# mppt.net
KiCad netlist of a schematic drawn in EAGLE
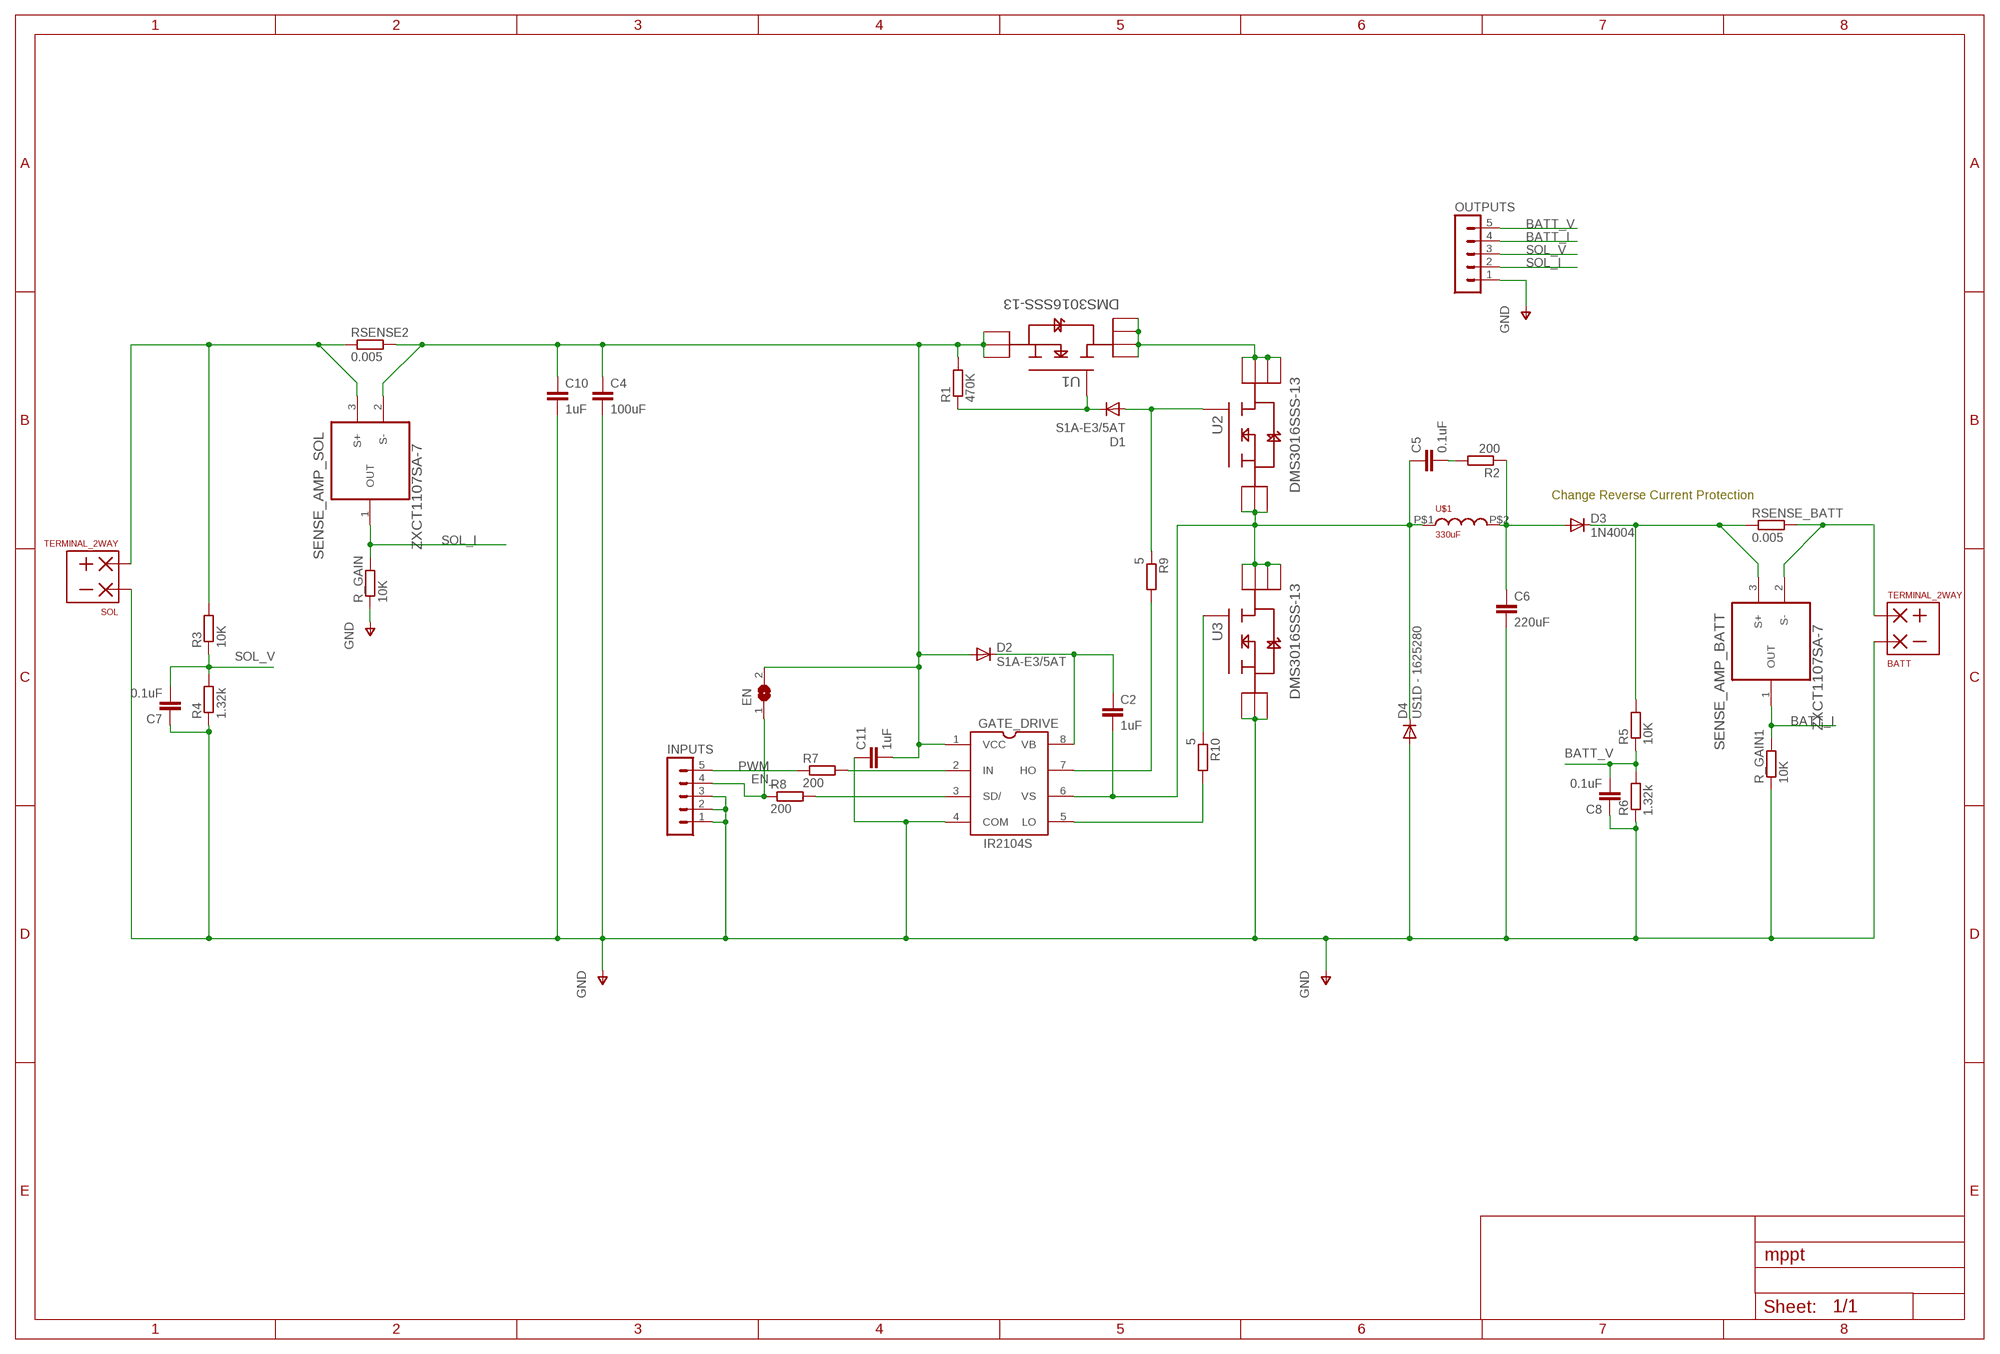
[diagram p0: schematic, sheet 1]

(export (version "E")
  (design (tool "Eeschema 10.0.6"))
  (components
    (comp (ref "BATT")
      (value "TERMINAL_2WAY")
      (footprint "eagle-import:TERMINAL_2WAY")
      (libsource (lib "eagle-import") (part "TERMINAL_2WAY"))
    )
    (comp (ref "C2")
      (value "1uF")
      (footprint "eagle-import:C0805K")
      (libsource (lib "eagle-import") (part "C-EUC0805K"))
    )
    (comp (ref "C4")
      (value "100uF")
      (footprint "eagle-import:C025-050X050")
      (libsource (lib "eagle-import") (part "C-EU025-050X050"))
    )
    (comp (ref "C5")
      (value "0.1uF")
      (footprint "eagle-import:C0805K")
      (libsource (lib "eagle-import") (part "C-EUC0805K"))
    )
    (comp (ref "C6")
      (value "220uF")
      (footprint "eagle-import:C025-050X050")
      (libsource (lib "eagle-import") (part "C-EU025-050X050"))
    )
    (comp (ref "C7")
      (value "0.1uF")
      (footprint "eagle-import:C0805K")
      (libsource (lib "eagle-import") (part "C-EUC0805K"))
    )
    (comp (ref "C8")
      (value "0.1uF")
      (footprint "eagle-import:C0805K")
      (libsource (lib "eagle-import") (part "C-EUC0805K"))
    )
    (comp (ref "C10")
      (value "1uF")
      (footprint "eagle-import:C0805K")
      (libsource (lib "eagle-import") (part "C-EUC0805K"))
    )
    (comp (ref "C11")
      (value "1uF")
      (footprint "eagle-import:C0805K")
      (libsource (lib "eagle-import") (part "C-EUC0805K"))
    )
    (comp (ref "D1")
      (value "S1A-E3/5AT")
      (footprint "eagle-import:DO-214AC")
      (libsource (lib "eagle-import") (part "DIODE-DO-214AC"))
    )
    (comp (ref "D2")
      (value "S1A-E3/5AT")
      (footprint "eagle-import:DO-214AC")
      (libsource (lib "eagle-import") (part "DIODE-DO-214AC"))
    )
    (comp (ref "D3")
      (value "1N4004")
      (footprint "eagle-import:DO41-10")
      (libsource (lib "eagle-import") (part "1N4004"))
    )
    (comp (ref "D4")
      (value "US1D - 1625280")
      (footprint "eagle-import:DO-214AC")
      (libsource (lib "eagle-import") (part "DIODE-DO-214AC"))
    )
    (comp (ref "EN") (value "SJ") (footprint "eagle-import:SJ") (libsource (lib "eagle-import") (part "SJ")))
    (comp (ref "GATE_DRIVE")
      (value "IR2104S")
      (footprint "eagle-import:IR2104S")
      (libsource (lib "eagle-import") (part "IR2104S"))
    )
    (comp (ref "INPUTS")
      (value "MA05-1")
      (footprint "eagle-import:MA05-1")
      (libsource (lib "eagle-import") (part "MA05-1"))
    )
    (comp (ref "OUTPUTS")
      (value "MA05-1")
      (footprint "eagle-import:MA05-1")
      (libsource (lib "eagle-import") (part "MA05-1"))
    )
    (comp (ref "R1")
      (value "470K")
      (footprint "eagle-import:M0805")
      (libsource (lib "eagle-import") (part "R-EU_M0805"))
    )
    (comp (ref "R2")
      (value "200")
      (footprint "eagle-import:M0805")
      (libsource (lib "eagle-import") (part "R-EU_M0805"))
    )
    (comp (ref "R3")
      (value "10K")
      (footprint "eagle-import:M0805")
      (libsource (lib "eagle-import") (part "R-EU_M0805"))
    )
    (comp (ref "R4")
      (value "1.32k")
      (footprint "eagle-import:M0805")
      (libsource (lib "eagle-import") (part "R-EU_M0805"))
    )
    (comp (ref "R5")
      (value "10K")
      (footprint "eagle-import:M0805")
      (libsource (lib "eagle-import") (part "R-EU_M0805"))
    )
    (comp (ref "R6")
      (value "1.32k")
      (footprint "eagle-import:M0805")
      (libsource (lib "eagle-import") (part "R-EU_M0805"))
    )
    (comp (ref "R7")
      (value "200")
      (footprint "eagle-import:M0805")
      (libsource (lib "eagle-import") (part "R-EU_M0805"))
    )
    (comp (ref "R8")
      (value "200")
      (footprint "eagle-import:M0805")
      (libsource (lib "eagle-import") (part "R-EU_M0805"))
    )
    (comp (ref "R9")
      (value "5")
      (footprint "eagle-import:M0805")
      (libsource (lib "eagle-import") (part "R-EU_M0805"))
    )
    (comp (ref "R10")
      (value "5")
      (footprint "eagle-import:M0805")
      (libsource (lib "eagle-import") (part "R-EU_M0805"))
    )
    (comp (ref "RSENSE2")
      (value "0.005")
      (footprint "eagle-import:R2512")
      (libsource (lib "eagle-import") (part "R-EU_R2512"))
    )
    (comp (ref "RSENSE_BATT")
      (value "0.005")
      (footprint "eagle-import:R2512")
      (libsource (lib "eagle-import") (part "R-EU_R2512"))
    )
    (comp (ref "R_GAIN")
      (value "10K")
      (footprint "eagle-import:M0805")
      (libsource (lib "eagle-import") (part "R-EU_M0805"))
    )
    (comp (ref "R_GAIN1")
      (value "10K")
      (footprint "eagle-import:M0805")
      (libsource (lib "eagle-import") (part "R-EU_M0805"))
    )
    (comp (ref "SENSE_AMP_BATT")
      (value "ZXCT1107SA-7")
      (footprint "eagle-import:SOT91P240X110-3N")
      (libsource (lib "eagle-import") (part "ZXCT1107SA-7"))
    )
    (comp (ref "SENSE_AMP_SOL")
      (value "ZXCT1107SA-7")
      (footprint "eagle-import:SOT91P240X110-3N")
      (libsource (lib "eagle-import") (part "ZXCT1107SA-7"))
    )
    (comp (ref "SOL")
      (value "TERMINAL_2WAY")
      (footprint "eagle-import:TERMINAL_2WAY")
      (libsource (lib "eagle-import") (part "TERMINAL_2WAY"))
    )
    (comp (ref "U$1")
      (value "330uF")
      (footprint "eagle-import:BOURNS_SDR1806")
      (libsource (lib "eagle-import") (part "INDUC_BOURNES_SDR1806"))
    )
    (comp (ref "U1")
      (value "DMS3016SSS-13")
      (footprint "eagle-import:SOIC127P600X175-8N")
      (libsource (lib "eagle-import") (part "DMS3016SSS-13"))
    )
    (comp (ref "U2")
      (value "DMS3016SSS-13")
      (footprint "eagle-import:SOIC127P600X175-8N")
      (libsource (lib "eagle-import") (part "DMS3016SSS-13"))
    )
    (comp (ref "U3")
      (value "DMS3016SSS-13")
      (footprint "eagle-import:SOIC127P600X175-8N")
      (libsource (lib "eagle-import") (part "DMS3016SSS-13"))
    )
  )
  (nets
    (net (code "1") (name "/BATT_I") (class "Default")
      (node (ref "OUTPUTS") (pin "4") (pinfunction "4_4") (pintype "passive"))
      (node (ref "R_GAIN1") (pin "2") (pinfunction "2_2") (pintype "passive"))
      (node (ref "SENSE_AMP_BATT") (pin "1") (pinfunction "OUT_1") (pintype "output"))
    )
    (net (code "2") (name "/BATT_V") (class "Default")
      (node (ref "C8") (pin "2") (pinfunction "2_2") (pintype "passive"))
      (node (ref "OUTPUTS") (pin "5") (pinfunction "5_5") (pintype "passive"))
      (node (ref "R5") (pin "1") (pinfunction "1_1") (pintype "passive"))
      (node (ref "R6") (pin "2") (pinfunction "2_2") (pintype "passive"))
    )
    (net (code "3") (name "/EN_") (class "Default")
      (node (ref "EN") (pin "1") (pinfunction "1_1") (pintype "passive"))
      (node (ref "INPUTS") (pin "4") (pinfunction "4_4") (pintype "passive"))
      (node (ref "R8") (pin "1") (pinfunction "1_1") (pintype "passive"))
    )
    (net (code "4") (name "/PWM") (class "Default")
      (node (ref "INPUTS") (pin "5") (pinfunction "5_5") (pintype "passive"))
      (node (ref "R7") (pin "1") (pinfunction "1_1") (pintype "passive"))
    )
    (net (code "5") (name "/SOL_I") (class "Default")
      (node (ref "OUTPUTS") (pin "2") (pinfunction "2_2") (pintype "passive"))
      (node (ref "R_GAIN") (pin "2") (pinfunction "2_2") (pintype "passive"))
      (node (ref "SENSE_AMP_SOL") (pin "1") (pinfunction "OUT_1") (pintype "output"))
    )
    (net (code "6") (name "/SOL_V") (class "Default")
      (node (ref "C7") (pin "2") (pinfunction "2_2") (pintype "passive"))
      (node (ref "OUTPUTS") (pin "3") (pinfunction "3_3") (pintype "passive"))
      (node (ref "R3") (pin "1") (pinfunction "1_1") (pintype "passive"))
      (node (ref "R4") (pin "2") (pinfunction "2_2") (pintype "passive"))
    )
    (net (code "7") (name "GND") (class "Default")
      (node (ref "BATT") (pin "P$2") (pinfunction "P$2_P$2") (pintype "bidirectional"))
      (node (ref "C10") (pin "2") (pinfunction "2_2") (pintype "passive"))
      (node (ref "C11") (pin "1") (pinfunction "1_1") (pintype "passive"))
      (node (ref "C4") (pin "2") (pinfunction "2_2") (pintype "passive"))
      (node (ref "C6") (pin "2") (pinfunction "2_2") (pintype "passive"))
      (node (ref "C7") (pin "1") (pinfunction "1_1") (pintype "passive"))
      (node (ref "C8") (pin "1") (pinfunction "1_1") (pintype "passive"))
      (node (ref "D4") (pin "A") (pinfunction "A_A") (pintype "passive"))
      (node (ref "GATE_DRIVE") (pin "4") (pinfunction "COM_4") (pintype "bidirectional"))
      (node (ref "INPUTS") (pin "1") (pinfunction "1_1") (pintype "passive"))
      (node (ref "INPUTS") (pin "2") (pinfunction "2_2") (pintype "passive"))
      (node (ref "INPUTS") (pin "3") (pinfunction "3_3") (pintype "passive"))
      (node (ref "OUTPUTS") (pin "1") (pinfunction "1_1") (pintype "passive"))
      (node (ref "R4") (pin "1") (pinfunction "1_1") (pintype "passive"))
      (node (ref "R6") (pin "1") (pinfunction "1_1") (pintype "passive"))
      (node (ref "R_GAIN") (pin "1") (pinfunction "1_1") (pintype "passive"))
      (node (ref "R_GAIN1") (pin "1") (pinfunction "1_1") (pintype "passive"))
      (node (ref "SOL") (pin "P$2") (pinfunction "P$2_P$2") (pintype "bidirectional"))
      (node (ref "U3") (pin "1") (pinfunction "S_2_1") (pintype "passive"))
      (node (ref "U3") (pin "2") (pinfunction "S_3_2") (pintype "passive"))
      (node (ref "U3") (pin "3") (pinfunction "S_3") (pintype "passive"))
    )
    (net (code "8") (name "Net-(C5-Pad2)") (class "Default")
      (node (ref "C5") (pin "2") (pinfunction "2_2") (pintype "passive"))
      (node (ref "R2") (pin "2") (pinfunction "2_2") (pintype "passive"))
    )
    (net (code "9") (name "Net-(C6-Pad1)") (class "Default")
      (node (ref "C6") (pin "1") (pinfunction "1_1") (pintype "passive"))
      (node (ref "D3") (pin "A") (pinfunction "A_A") (pintype "passive"))
      (node (ref "R2") (pin "1") (pinfunction "1_1") (pintype "passive"))
      (node (ref "U$1") (pin "P$2") (pinfunction "P$2_P$2") (pintype "bidirectional"))
    )
    (net (code "10") (name "Net-(GATE_DRIVE-HO)") (class "Default")
      (node (ref "GATE_DRIVE") (pin "7") (pinfunction "HO_7") (pintype "bidirectional"))
      (node (ref "R9") (pin "2") (pinfunction "2_2") (pintype "passive"))
    )
    (net (code "11") (name "Net-(GATE_DRIVE-IN)") (class "Default")
      (node (ref "GATE_DRIVE") (pin "2") (pinfunction "IN_2") (pintype "bidirectional"))
      (node (ref "R7") (pin "2") (pinfunction "2_2") (pintype "passive"))
    )
    (net (code "12") (name "Net-(GATE_DRIVE-LO)") (class "Default")
      (node (ref "GATE_DRIVE") (pin "5") (pinfunction "LO_5") (pintype "bidirectional"))
      (node (ref "R10") (pin "2") (pinfunction "2_2") (pintype "passive"))
    )
    (net (code "13") (name "Net-(GATE_DRIVE-SD{slash})") (class "Default")
      (node (ref "GATE_DRIVE") (pin "3") (pinfunction "SD/_3") (pintype "bidirectional"))
      (node (ref "R8") (pin "2") (pinfunction "2_2") (pintype "passive"))
    )
    (net (code "14") (name "Net-(GATE_DRIVE-VB)") (class "Default")
      (node (ref "C2") (pin "1") (pinfunction "1_1") (pintype "passive"))
      (node (ref "D2") (pin "C") (pinfunction "C_C") (pintype "passive"))
      (node (ref "GATE_DRIVE") (pin "8") (pinfunction "VB_8") (pintype "power_in"))
    )
    (net (code "15") (name "Net-(GATE_DRIVE-VCC)") (class "Default")
      (node (ref "C10") (pin "1") (pinfunction "1_1") (pintype "passive"))
      (node (ref "C11") (pin "2") (pinfunction "2_2") (pintype "passive"))
      (node (ref "C4") (pin "1") (pinfunction "1_1") (pintype "passive"))
      (node (ref "D2") (pin "A") (pinfunction "A_A") (pintype "passive"))
      (node (ref "EN") (pin "2") (pinfunction "2_2") (pintype "passive"))
      (node (ref "GATE_DRIVE") (pin "1") (pinfunction "VCC_1") (pintype "power_in"))
      (node (ref "R1") (pin "2") (pinfunction "2_2") (pintype "passive"))
      (node (ref "RSENSE2") (pin "2") (pinfunction "2_2") (pintype "passive"))
      (node (ref "SENSE_AMP_SOL") (pin "2") (pinfunction "S-_2") (pintype "input"))
      (node (ref "U1") (pin "1") (pinfunction "S_2_1") (pintype "passive"))
      (node (ref "U1") (pin "2") (pinfunction "S_3_2") (pintype "passive"))
      (node (ref "U1") (pin "3") (pinfunction "S_3") (pintype "passive"))
    )
    (net (code "16") (name "Net-(GATE_DRIVE-VS)") (class "Default")
      (node (ref "C2") (pin "2") (pinfunction "2_2") (pintype "passive"))
      (node (ref "C5") (pin "1") (pinfunction "1_1") (pintype "passive"))
      (node (ref "D4") (pin "C") (pinfunction "C_C") (pintype "passive"))
      (node (ref "GATE_DRIVE") (pin "6") (pinfunction "VS_6") (pintype "power_in"))
      (node (ref "U$1") (pin "P$1") (pinfunction "P$1_P$1") (pintype "bidirectional"))
      (node (ref "U2") (pin "1") (pinfunction "S_2_1") (pintype "passive"))
      (node (ref "U2") (pin "2") (pinfunction "S_3_2") (pintype "passive"))
      (node (ref "U2") (pin "3") (pinfunction "S_3") (pintype "passive"))
      (node (ref "U3") (pin "5") (pinfunction "D_3_5") (pintype "passive"))
      (node (ref "U3") (pin "6") (pinfunction "D_2_6") (pintype "passive"))
      (node (ref "U3") (pin "7") (pinfunction "D_4_7") (pintype "passive"))
      (node (ref "U3") (pin "8") (pinfunction "D_8") (pintype "passive"))
    )
    (net (code "17") (name "Net-(SENSE_AMP_BATT-S+)") (class "Default")
      (node (ref "D3") (pin "C") (pinfunction "C_C") (pintype "passive"))
      (node (ref "R5") (pin "2") (pinfunction "2_2") (pintype "passive"))
      (node (ref "RSENSE_BATT") (pin "1") (pinfunction "1_1") (pintype "passive"))
      (node (ref "SENSE_AMP_BATT") (pin "3") (pinfunction "S+_3") (pintype "input"))
    )
    (net (code "18") (name "Net-(SENSE_AMP_BATT-S-)") (class "Default")
      (node (ref "BATT") (pin "P$1") (pinfunction "P$1_P$1") (pintype "bidirectional"))
      (node (ref "RSENSE_BATT") (pin "2") (pinfunction "2_2") (pintype "passive"))
      (node (ref "SENSE_AMP_BATT") (pin "2") (pinfunction "S-_2") (pintype "input"))
    )
    (net (code "19") (name "Net-(SENSE_AMP_SOL-S+)") (class "Default")
      (node (ref "R3") (pin "2") (pinfunction "2_2") (pintype "passive"))
      (node (ref "RSENSE2") (pin "1") (pinfunction "1_1") (pintype "passive"))
      (node (ref "SENSE_AMP_SOL") (pin "3") (pinfunction "S+_3") (pintype "input"))
      (node (ref "SOL") (pin "P$1") (pinfunction "P$1_P$1") (pintype "bidirectional"))
    )
    (net (code "20") (name "Net-(U1-D)") (class "Default")
      (node (ref "U1") (pin "5") (pinfunction "D_3_5") (pintype "passive"))
      (node (ref "U1") (pin "6") (pinfunction "D_2_6") (pintype "passive"))
      (node (ref "U1") (pin "7") (pinfunction "D_4_7") (pintype "passive"))
      (node (ref "U1") (pin "8") (pinfunction "D_8") (pintype "passive"))
      (node (ref "U2") (pin "5") (pinfunction "D_3_5") (pintype "passive"))
      (node (ref "U2") (pin "6") (pinfunction "D_2_6") (pintype "passive"))
      (node (ref "U2") (pin "7") (pinfunction "D_4_7") (pintype "passive"))
      (node (ref "U2") (pin "8") (pinfunction "D_8") (pintype "passive"))
    )
    (net (code "21") (name "Net-(U1-G)") (class "Default")
      (node (ref "D1") (pin "C") (pinfunction "C_C") (pintype "passive"))
      (node (ref "R1") (pin "1") (pinfunction "1_1") (pintype "passive"))
      (node (ref "U1") (pin "4") (pinfunction "G_4") (pintype "passive"))
    )
    (net (code "22") (name "Net-(U2-G)") (class "Default")
      (node (ref "D1") (pin "A") (pinfunction "A_A") (pintype "passive"))
      (node (ref "R9") (pin "1") (pinfunction "1_1") (pintype "passive"))
      (node (ref "U2") (pin "4") (pinfunction "G_4") (pintype "passive"))
    )
    (net (code "23") (name "Net-(U3-G)") (class "Default")
      (node (ref "R10") (pin "1") (pinfunction "1_1") (pintype "passive"))
      (node (ref "U3") (pin "4") (pinfunction "G_4") (pintype "passive"))
    )
  )
)
